# meduza01.net
KiCad netlist of a schematic drawn in EAGLE
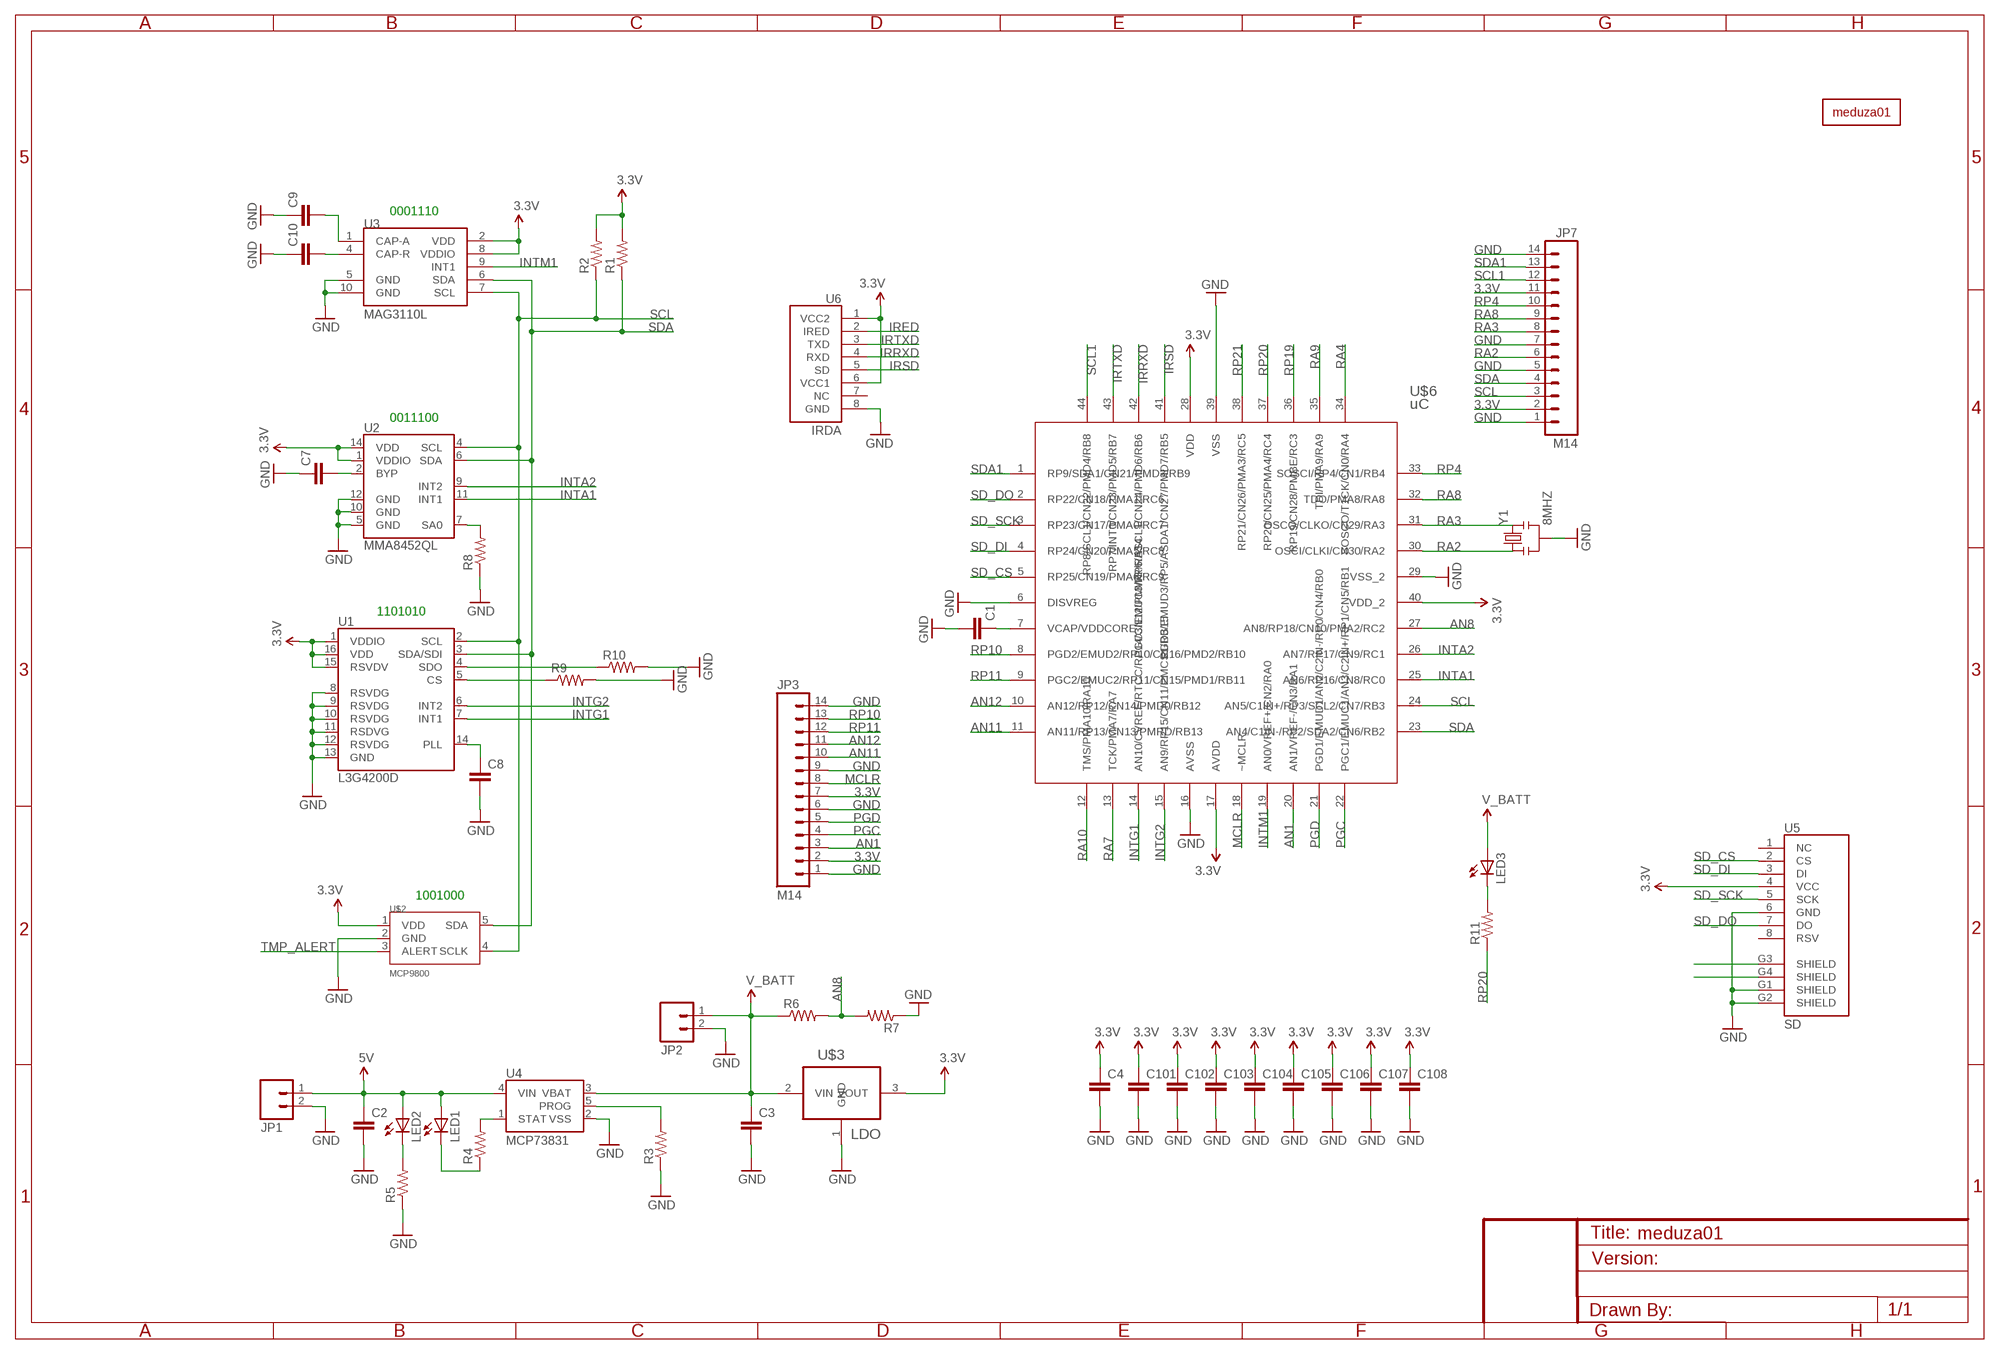
[diagram p0: schematic, sheet 1]

(export (version "E")
  (design (tool "Eeschema 10.0.6"))
  (components
    (comp (ref "C1")
      (value "CAP0603")
      (footprint "eagle-import:0603")
      (libsource (lib "eagle-import") (part "CAP0603"))
    )
    (comp (ref "C2")
      (value "CAP0805")
      (footprint "eagle-import:0805")
      (libsource (lib "eagle-import") (part "SparkFun-Passives_CAP0805"))
    )
    (comp (ref "C3")
      (value "CAP0805")
      (footprint "eagle-import:0805")
      (libsource (lib "eagle-import") (part "SparkFun-Passives_CAP0805"))
    )
    (comp (ref "C4")
      (value "CAP0603")
      (footprint "eagle-import:0603")
      (libsource (lib "eagle-import") (part "CAP0603"))
    )
    (comp (ref "C7")
      (value "CAP0603")
      (footprint "eagle-import:0603")
      (libsource (lib "eagle-import") (part "CAP0603"))
    )
    (comp (ref "C8")
      (value "CAP0603")
      (footprint "eagle-import:0603")
      (libsource (lib "eagle-import") (part "CAP0603"))
    )
    (comp (ref "C9")
      (value "CAP0603")
      (footprint "eagle-import:0603")
      (libsource (lib "eagle-import") (part "CAP0603"))
    )
    (comp (ref "C10")
      (value "CAP0603")
      (footprint "eagle-import:0603")
      (libsource (lib "eagle-import") (part "CAP0603"))
    )
    (comp (ref "C101")
      (value "CAP0603")
      (footprint "eagle-import:0603")
      (libsource (lib "eagle-import") (part "CAP0603"))
    )
    (comp (ref "C102")
      (value "CAP0603")
      (footprint "eagle-import:0603")
      (libsource (lib "eagle-import") (part "CAP0603"))
    )
    (comp (ref "C103")
      (value "CAP0603")
      (footprint "eagle-import:0603")
      (libsource (lib "eagle-import") (part "CAP0603"))
    )
    (comp (ref "C104")
      (value "CAP0603")
      (footprint "eagle-import:0603")
      (libsource (lib "eagle-import") (part "CAP0603"))
    )
    (comp (ref "C105")
      (value "CAP0603")
      (footprint "eagle-import:0603")
      (libsource (lib "eagle-import") (part "CAP0603"))
    )
    (comp (ref "C106")
      (value "CAP0603")
      (footprint "eagle-import:0603")
      (libsource (lib "eagle-import") (part "CAP0603"))
    )
    (comp (ref "C107")
      (value "CAP0603")
      (footprint "eagle-import:0603")
      (libsource (lib "eagle-import") (part "CAP0603"))
    )
    (comp (ref "C108")
      (value "CAP0603")
      (footprint "eagle-import:0603")
      (libsource (lib "eagle-import") (part "CAP0603"))
    )
    (comp (ref "JP1")
      (value "M02PTH")
      (footprint "eagle-import:1X02")
      (libsource (lib "eagle-import") (part "M02PTH"))
    )
    (comp (ref "JP2")
      (value "M02PTH")
      (footprint "eagle-import:1X02")
      (libsource (lib "eagle-import") (part "M02PTH"))
    )
    (comp (ref "JP3")
      (value "M14")
      (footprint "eagle-import:1X14")
      (libsource (lib "eagle-import") (part "M14"))
    )
    (comp (ref "JP7")
      (value "M14")
      (footprint "eagle-import:1X14")
      (libsource (lib "eagle-import") (part "M14"))
    )
    (comp (ref "LED1")
      (value "LED1206")
      (footprint "eagle-import:LED-1206")
      (libsource (lib "eagle-import") (part "LED1206"))
    )
    (comp (ref "LED2")
      (value "LED1206")
      (footprint "eagle-import:LED-1206")
      (libsource (lib "eagle-import") (part "LED1206"))
    )
    (comp (ref "LED3")
      (value "LED1206")
      (footprint "eagle-import:LED-1206")
      (libsource (lib "eagle-import") (part "LED1206"))
    )
    (comp (ref "R1")
      (value "RESISTOR0603")
      (footprint "eagle-import:0603")
      (libsource (lib "eagle-import") (part "RESISTOR0603"))
    )
    (comp (ref "R2")
      (value "RESISTOR0603")
      (footprint "eagle-import:0603")
      (libsource (lib "eagle-import") (part "RESISTOR0603"))
    )
    (comp (ref "R3")
      (value "RESISTOR0603")
      (footprint "eagle-import:0603")
      (libsource (lib "eagle-import") (part "RESISTOR0603"))
    )
    (comp (ref "R4")
      (value "RESISTOR0603")
      (footprint "eagle-import:0603")
      (libsource (lib "eagle-import") (part "RESISTOR0603"))
    )
    (comp (ref "R5")
      (value "RESISTOR0603")
      (footprint "eagle-import:0603")
      (libsource (lib "eagle-import") (part "RESISTOR0603"))
    )
    (comp (ref "R6")
      (value "RESISTOR0603")
      (footprint "eagle-import:0603")
      (libsource (lib "eagle-import") (part "RESISTOR0603"))
    )
    (comp (ref "R7")
      (value "RESISTOR0603")
      (footprint "eagle-import:0603")
      (libsource (lib "eagle-import") (part "RESISTOR0603"))
    )
    (comp (ref "R8")
      (value "RESISTOR0603")
      (footprint "eagle-import:0603")
      (libsource (lib "eagle-import") (part "RESISTOR0603"))
    )
    (comp (ref "R9")
      (value "RESISTOR0603")
      (footprint "eagle-import:0603")
      (libsource (lib "eagle-import") (part "RESISTOR0603"))
    )
    (comp (ref "R10")
      (value "RESISTOR0603")
      (footprint "eagle-import:0603")
      (libsource (lib "eagle-import") (part "RESISTOR0603"))
    )
    (comp (ref "R11")
      (value "RESISTOR0603")
      (footprint "eagle-import:0603")
      (libsource (lib "eagle-import") (part "RESISTOR0603"))
    )
    (comp (ref "U$1")
      (value "MEDUZA01")
      (footprint "eagle-import:MEDUZA01")
      (libsource (lib "eagle-import") (part "MEDUZA01"))
    )
    (comp (ref "U$2")
      (value "MCP9800")
      (footprint "eagle-import:SOT23-5")
      (libsource (lib "eagle-import") (part "MCP9800"))
    )
    (comp (ref "U$3")
      (value "LDO")
      (footprint "eagle-import:SOT89R")
      (libsource (lib "eagle-import") (part "MCP1700T-3302E/TTSOT89MCP1700-3N"))
    )
    (comp (ref "U$6")
      (value "uC")
      (footprint "eagle-import:QFP80P1200X1200X120-44N")
      (fields (field (name "MPN") "PIC24FJ64GA004-I/PT"))
      (libsource (lib "eagle-import") (part "PIC24FJ64GA004"))
    )
    (comp (ref "U1")
      (value "L3G4200D")
      (footprint "eagle-import:LGA16-4X4")
      (libsource (lib "eagle-import") (part "L3G4200D"))
    )
    (comp (ref "U2")
      (value "MMA8452QL")
      (footprint "eagle-import:QFN-16_0.5MM-EXTRA")
      (libsource (lib "eagle-import") (part "MMA8452QL"))
    )
    (comp (ref "U3")
      (value "MAG3110L")
      (footprint "eagle-import:DFN-10-EXTRA")
      (libsource (lib "eagle-import") (part "MAG3110L"))
    )
    (comp (ref "U4")
      (value "MCP73831")
      (footprint "eagle-import:SOT23-5")
      (libsource (lib "eagle-import") (part "MCP73831"))
    )
    (comp (ref "U5")
      (value "SD")
      (footprint "eagle-import:MOLEX-SD-47309")
      (libsource (lib "eagle-import") (part "USD-SOCKETMOLEX47309"))
    )
    (comp (ref "U6")
      (value "IRDA")
      (footprint "eagle-import:TFDU6300")
      (libsource (lib "eagle-import") (part "TFDU6300TFDU6300"))
    )
    (comp (ref "Y1")
      (value "8MHZ")
      (footprint "eagle-import:RESONATOR-SMD")
      (libsource (lib "eagle-import") (part "RESONATOR8MHZ"))
    )
  )
  (nets
    (net (code "1") (name "/AN1") (class "Default")
      (node (ref "JP3") (pin "3") (pinfunction "3_3") (pintype "passive"))
      (node (ref "U$6") (pin "20") (pinfunction "AN1/VREF-/CN3/RA1_20") (pintype "bidirectional"))
    )
    (net (code "2") (name "/AN8") (class "Default")
      (node (ref "R6") (pin "2") (pinfunction "2_2") (pintype "passive"))
      (node (ref "R7") (pin "2") (pinfunction "2_2") (pintype "passive"))
      (node (ref "U$6") (pin "27") (pinfunction "AN8/RP18/CN10/PMA2/RC2_27") (pintype "bidirectional"))
    )
    (net (code "3") (name "/AN11") (class "Default")
      (node (ref "JP3") (pin "10") (pinfunction "10_10") (pintype "passive"))
      (node (ref "U$6") (pin "11") (pinfunction "AN11/RP13/CN13/PMRD/RB13_11") (pintype "bidirectional"))
    )
    (net (code "4") (name "/AN12") (class "Default")
      (node (ref "JP3") (pin "11") (pinfunction "11_11") (pintype "passive"))
      (node (ref "U$6") (pin "10") (pinfunction "AN12/RP12/CN14/PMD0/RB12_10") (pintype "bidirectional"))
    )
    (net (code "5") (name "/INTA1") (class "Default")
      (node (ref "U$6") (pin "25") (pinfunction "AN6/RP16/CN8/RC0_25") (pintype "bidirectional"))
      (node (ref "U2") (pin "11") (pinfunction "INT1_11") (pintype "bidirectional"))
    )
    (net (code "6") (name "/INTA2") (class "Default")
      (node (ref "U$6") (pin "26") (pinfunction "AN7/RP17/CN9/RC1_26") (pintype "bidirectional"))
      (node (ref "U2") (pin "9") (pinfunction "INT2_9") (pintype "bidirectional"))
    )
    (net (code "7") (name "/INTG1") (class "Default")
      (node (ref "U$6") (pin "14") (pinfunction "AN10/CVREF/RTCC/RP14/CN12/PMWR/RB14_14") (pintype "bidirectional"))
      (node (ref "U1") (pin "7") (pinfunction "INT1_7") (pintype "bidirectional"))
    )
    (net (code "8") (name "/INTG2") (class "Default")
      (node (ref "U$6") (pin "15") (pinfunction "AN9/RP15/CN11/PMCS1/RB15_15") (pintype "bidirectional"))
      (node (ref "U1") (pin "6") (pinfunction "INT2_6") (pintype "bidirectional"))
    )
    (net (code "9") (name "/INTM1") (class "Default")
      (node (ref "U$6") (pin "19") (pinfunction "AN0/VREF+/CN2/RA0_19") (pintype "bidirectional"))
      (node (ref "U3") (pin "9") (pinfunction "INT1_9") (pintype "bidirectional"))
    )
    (net (code "10") (name "/IRED") (class "Default")
      (node (ref "U6") (pin "2") (pinfunction "IRED_2") (pintype "bidirectional"))
    )
    (net (code "11") (name "/IRRXD") (class "Default")
      (node (ref "U$6") (pin "42") (pinfunction "PGC3/EMUC3/RP6/ASCL1/CN24/PMD6/RB6_42") (pintype "bidirectional"))
      (node (ref "U6") (pin "4") (pinfunction "RXD_4") (pintype "bidirectional"))
    )
    (net (code "12") (name "/IRSD") (class "Default")
      (node (ref "U$6") (pin "41") (pinfunction "PGD3/EMUD3/RP5/ASDA1/CN27/PMD7/RB5_41") (pintype "bidirectional"))
      (node (ref "U6") (pin "5") (pinfunction "SD_5") (pintype "bidirectional"))
    )
    (net (code "13") (name "/IRTXD") (class "Default")
      (node (ref "U$6") (pin "43") (pinfunction "RP7/INT0/CN23/PMD5/RB7_43") (pintype "bidirectional"))
      (node (ref "U6") (pin "3") (pinfunction "TXD_3") (pintype "bidirectional"))
    )
    (net (code "14") (name "/MCLR") (class "Default")
      (node (ref "JP3") (pin "8") (pinfunction "8_8") (pintype "passive"))
      (node (ref "U$6") (pin "18") (pinfunction "~{MCLR}_18") (pintype "bidirectional"))
    )
    (net (code "15") (name "/PGC") (class "Default")
      (node (ref "JP3") (pin "4") (pinfunction "4_4") (pintype "passive"))
      (node (ref "U$6") (pin "22") (pinfunction "PGC1/EMUC1/AN3/C2IN+/RP1/CN5/RB1_22") (pintype "bidirectional"))
    )
    (net (code "16") (name "/PGD") (class "Default")
      (node (ref "JP3") (pin "5") (pinfunction "5_5") (pintype "passive"))
      (node (ref "U$6") (pin "21") (pinfunction "PGD1/EMUD1/AN2/C2IN-/RP0/CN4/RB0_21") (pintype "bidirectional"))
    )
    (net (code "17") (name "/RA2") (class "Default")
      (node (ref "JP7") (pin "6") (pinfunction "6_6") (pintype "passive"))
      (node (ref "U$6") (pin "30") (pinfunction "OSCI/CLKI/CN30/RA2_30") (pintype "bidirectional"))
      (node (ref "Y1") (pin "1") (pinfunction "1_1") (pintype "passive"))
    )
    (net (code "18") (name "/RA3") (class "Default")
      (node (ref "JP7") (pin "8") (pinfunction "8_8") (pintype "passive"))
      (node (ref "U$6") (pin "31") (pinfunction "OSCO/CLKO/CN29/RA3_31") (pintype "bidirectional"))
      (node (ref "Y1") (pin "3") (pinfunction "3_3") (pintype "passive"))
    )
    (net (code "19") (name "/RA4") (class "Default")
      (node (ref "U$6") (pin "34") (pinfunction "SOSCO/T1CK/CN0/RA4_34") (pintype "bidirectional"))
    )
    (net (code "20") (name "/RA7") (class "Default")
      (node (ref "U$6") (pin "13") (pinfunction "TCK/PMA7/RA7_13") (pintype "bidirectional"))
    )
    (net (code "21") (name "/RA8") (class "Default")
      (node (ref "JP7") (pin "9") (pinfunction "9_9") (pintype "passive"))
      (node (ref "U$6") (pin "32") (pinfunction "TDO/PMA8/RA8_32") (pintype "bidirectional"))
    )
    (net (code "22") (name "/RA9") (class "Default")
      (node (ref "U$6") (pin "35") (pinfunction "TDI/PMA9/RA9_35") (pintype "bidirectional"))
    )
    (net (code "23") (name "/RA10") (class "Default")
      (node (ref "U$6") (pin "12") (pinfunction "TMS/PMA10/RA10_12") (pintype "bidirectional"))
    )
    (net (code "24") (name "/RP4") (class "Default")
      (node (ref "JP7") (pin "10") (pinfunction "10_10") (pintype "passive"))
      (node (ref "U$6") (pin "33") (pinfunction "SOSCI/RP4/CN1/RB4_33") (pintype "bidirectional"))
    )
    (net (code "25") (name "/RP10") (class "Default")
      (node (ref "JP3") (pin "13") (pinfunction "13_13") (pintype "passive"))
      (node (ref "U$6") (pin "8") (pinfunction "PGD2/EMUD2/RP10/CN16/PMD2/RB10_8") (pintype "bidirectional"))
    )
    (net (code "26") (name "/RP11") (class "Default")
      (node (ref "JP3") (pin "12") (pinfunction "12_12") (pintype "passive"))
      (node (ref "U$6") (pin "9") (pinfunction "PGC2/EMUC2/RP11/CN15/PMD1/RB11_9") (pintype "bidirectional"))
    )
    (net (code "27") (name "/RP19") (class "Default")
      (node (ref "U$6") (pin "36") (pinfunction "RP19/CN28/PMBE/RC3_36") (pintype "bidirectional"))
    )
    (net (code "28") (name "/RP20") (class "Default")
      (node (ref "R11") (pin "1") (pinfunction "1_1") (pintype "passive"))
      (node (ref "U$6") (pin "37") (pinfunction "RP20/CN25/PMA4/RC4_37") (pintype "bidirectional"))
    )
    (net (code "29") (name "/RP21") (class "Default")
      (node (ref "U$6") (pin "38") (pinfunction "RP21/CN26/PMA3/RC5_38") (pintype "bidirectional"))
    )
    (net (code "30") (name "/SCL") (class "Default")
      (node (ref "JP7") (pin "3") (pinfunction "3_3") (pintype "passive"))
      (node (ref "R2") (pin "1") (pinfunction "1_1") (pintype "passive"))
      (node (ref "U$2") (pin "4") (pinfunction "SCLK_4") (pintype "input"))
      (node (ref "U$6") (pin "24") (pinfunction "AN5/C1IN+/RP3/SCL2/CN7/RB3_24") (pintype "bidirectional"))
      (node (ref "U1") (pin "2") (pinfunction "SCL_2") (pintype "bidirectional"))
      (node (ref "U2") (pin "4") (pinfunction "SCL_4") (pintype "bidirectional"))
      (node (ref "U3") (pin "7") (pinfunction "SCL_7") (pintype "bidirectional"))
    )
    (net (code "31") (name "/SCL1") (class "Default")
      (node (ref "JP7") (pin "12") (pinfunction "12_12") (pintype "passive"))
      (node (ref "U$6") (pin "44") (pinfunction "RP8/SCL1/CN22/PMD4/RB8_44") (pintype "bidirectional"))
    )
    (net (code "32") (name "/SDA") (class "Default")
      (node (ref "JP7") (pin "4") (pinfunction "4_4") (pintype "passive"))
      (node (ref "R1") (pin "1") (pinfunction "1_1") (pintype "passive"))
      (node (ref "U$2") (pin "5") (pinfunction "SDA_5") (pintype "bidirectional"))
      (node (ref "U$6") (pin "23") (pinfunction "AN4/C1IN-/RP2/SDA2/CN6/RB2_23") (pintype "bidirectional"))
      (node (ref "U1") (pin "3") (pinfunction "SDA/SDI_3") (pintype "bidirectional"))
      (node (ref "U2") (pin "6") (pinfunction "SDA_6") (pintype "bidirectional"))
      (node (ref "U3") (pin "6") (pinfunction "SDA_6") (pintype "bidirectional"))
    )
    (net (code "33") (name "/SDA1") (class "Default")
      (node (ref "JP7") (pin "13") (pinfunction "13_13") (pintype "passive"))
      (node (ref "U$6") (pin "1") (pinfunction "RP9/SDA1/CN21/PMD3/RB9_1") (pintype "bidirectional"))
    )
    (net (code "34") (name "/SD_CS") (class "Default")
      (node (ref "U$6") (pin "5") (pinfunction "RP25/CN19/PMA6/RC9_5") (pintype "bidirectional"))
      (node (ref "U5") (pin "2") (pinfunction "CS_2") (pintype "bidirectional"))
    )
    (net (code "35") (name "/SD_DI") (class "Default")
      (node (ref "U$6") (pin "4") (pinfunction "RP24/CN20/PMA5/RC8_4") (pintype "bidirectional"))
      (node (ref "U5") (pin "3") (pinfunction "DI_3") (pintype "bidirectional"))
    )
    (net (code "36") (name "/SD_DO") (class "Default")
      (node (ref "U$6") (pin "2") (pinfunction "RP22/CN18/PMA1/RC6_2") (pintype "bidirectional"))
      (node (ref "U5") (pin "7") (pinfunction "DO_7") (pintype "bidirectional"))
    )
    (net (code "37") (name "/SD_SCK") (class "Default")
      (node (ref "U$6") (pin "3") (pinfunction "RP23/CN17/PMA0/RC7_3") (pintype "bidirectional"))
      (node (ref "U5") (pin "5") (pinfunction "SCK_5") (pintype "bidirectional"))
    )
    (net (code "38") (name "/TMP_ALERT") (class "Default")
      (node (ref "U$2") (pin "3") (pinfunction "ALERT_3") (pintype "output"))
    )
    (net (code "39") (name "3.3V") (class "Default")
      (node (ref "C101") (pin "1") (pinfunction "1_1") (pintype "passive"))
      (node (ref "C102") (pin "1") (pinfunction "1_1") (pintype "passive"))
      (node (ref "C103") (pin "1") (pinfunction "1_1") (pintype "passive"))
      (node (ref "C104") (pin "1") (pinfunction "1_1") (pintype "passive"))
      (node (ref "C105") (pin "1") (pinfunction "1_1") (pintype "passive"))
      (node (ref "C106") (pin "1") (pinfunction "1_1") (pintype "passive"))
      (node (ref "C107") (pin "1") (pinfunction "1_1") (pintype "passive"))
      (node (ref "C108") (pin "1") (pinfunction "1_1") (pintype "passive"))
      (node (ref "C4") (pin "1") (pinfunction "1_1") (pintype "passive"))
      (node (ref "JP3") (pin "2") (pinfunction "2_2") (pintype "passive"))
      (node (ref "JP3") (pin "7") (pinfunction "7_7") (pintype "passive"))
      (node (ref "JP7") (pin "11") (pinfunction "11_11") (pintype "passive"))
      (node (ref "JP7") (pin "2") (pinfunction "2_2") (pintype "passive"))
      (node (ref "R1") (pin "2") (pinfunction "2_2") (pintype "passive"))
      (node (ref "R2") (pin "2") (pinfunction "2_2") (pintype "passive"))
      (node (ref "U$2") (pin "1") (pinfunction "VDD_1") (pintype "power_in"))
      (node (ref "U$3") (pin "3") (pinfunction "VOUT_3") (pintype "output"))
      (node (ref "U$6") (pin "17") (pinfunction "AVDD_17") (pintype "power_in"))
      (node (ref "U$6") (pin "28") (pinfunction "VDD_28") (pintype "power_in"))
      (node (ref "U$6") (pin "40") (pinfunction "VDD_2_40") (pintype "power_in"))
      (node (ref "U1") (pin "1") (pinfunction "VDDIO_1") (pintype "bidirectional"))
      (node (ref "U1") (pin "15") (pinfunction "RSVDV_15") (pintype "bidirectional"))
      (node (ref "U1") (pin "16") (pinfunction "VDD_16") (pintype "bidirectional"))
      (node (ref "U2") (pin "1") (pinfunction "VDDIO_1") (pintype "bidirectional"))
      (node (ref "U2") (pin "14") (pinfunction "VDD_14") (pintype "bidirectional"))
      (node (ref "U3") (pin "2") (pinfunction "VDD_2") (pintype "bidirectional"))
      (node (ref "U3") (pin "8") (pinfunction "VDDIO_8") (pintype "bidirectional"))
      (node (ref "U5") (pin "4") (pinfunction "VCC_4") (pintype "bidirectional"))
      (node (ref "U6") (pin "1") (pinfunction "VCC2_1") (pintype "bidirectional"))
      (node (ref "U6") (pin "6") (pinfunction "VCC1_6") (pintype "bidirectional"))
    )
    (net (code "40") (name "5V") (class "Default")
      (node (ref "C2") (pin "1") (pinfunction "1_1") (pintype "passive"))
      (node (ref "JP1") (pin "1") (pinfunction "1_1") (pintype "passive"))
      (node (ref "LED1") (pin "A") (pinfunction "A_A") (pintype "passive"))
      (node (ref "LED2") (pin "A") (pinfunction "A_A") (pintype "passive"))
      (node (ref "U4") (pin "4") (pinfunction "VIN_4") (pintype "power_in"))
    )
    (net (code "41") (name "GND") (class "Default")
      (node (ref "C1") (pin "2") (pinfunction "2_2") (pintype "passive"))
      (node (ref "C10") (pin "1") (pinfunction "1_1") (pintype "passive"))
      (node (ref "C101") (pin "2") (pinfunction "2_2") (pintype "passive"))
      (node (ref "C102") (pin "2") (pinfunction "2_2") (pintype "passive"))
      (node (ref "C103") (pin "2") (pinfunction "2_2") (pintype "passive"))
      (node (ref "C104") (pin "2") (pinfunction "2_2") (pintype "passive"))
      (node (ref "C105") (pin "2") (pinfunction "2_2") (pintype "passive"))
      (node (ref "C106") (pin "2") (pinfunction "2_2") (pintype "passive"))
      (node (ref "C107") (pin "2") (pinfunction "2_2") (pintype "passive"))
      (node (ref "C108") (pin "2") (pinfunction "2_2") (pintype "passive"))
      (node (ref "C2") (pin "2") (pinfunction "2_2") (pintype "passive"))
      (node (ref "C3") (pin "2") (pinfunction "2_2") (pintype "passive"))
      (node (ref "C4") (pin "2") (pinfunction "2_2") (pintype "passive"))
      (node (ref "C7") (pin "1") (pinfunction "1_1") (pintype "passive"))
      (node (ref "C8") (pin "2") (pinfunction "2_2") (pintype "passive"))
      (node (ref "C9") (pin "1") (pinfunction "1_1") (pintype "passive"))
      (node (ref "JP1") (pin "2") (pinfunction "2_2") (pintype "passive"))
      (node (ref "JP2") (pin "2") (pinfunction "2_2") (pintype "passive"))
      (node (ref "JP3") (pin "1") (pinfunction "1_1") (pintype "passive"))
      (node (ref "JP3") (pin "14") (pinfunction "14_14") (pintype "passive"))
      (node (ref "JP3") (pin "6") (pinfunction "6_6") (pintype "passive"))
      (node (ref "JP3") (pin "9") (pinfunction "9_9") (pintype "passive"))
      (node (ref "JP7") (pin "1") (pinfunction "1_1") (pintype "passive"))
      (node (ref "JP7") (pin "14") (pinfunction "14_14") (pintype "passive"))
      (node (ref "JP7") (pin "5") (pinfunction "5_5") (pintype "passive"))
      (node (ref "JP7") (pin "7") (pinfunction "7_7") (pintype "passive"))
      (node (ref "R10") (pin "2") (pinfunction "2_2") (pintype "passive"))
      (node (ref "R3") (pin "1") (pinfunction "1_1") (pintype "passive"))
      (node (ref "R5") (pin "1") (pinfunction "1_1") (pintype "passive"))
      (node (ref "R7") (pin "1") (pinfunction "1_1") (pintype "passive"))
      (node (ref "R8") (pin "1") (pinfunction "1_1") (pintype "passive"))
      (node (ref "R9") (pin "2") (pinfunction "2_2") (pintype "passive"))
      (node (ref "U$2") (pin "2") (pinfunction "GND_2") (pintype "passive"))
      (node (ref "U$3") (pin "1") (pinfunction "GND_1") (pintype "passive"))
      (node (ref "U$6") (pin "16") (pinfunction "AVSS_16") (pintype "power_in"))
      (node (ref "U$6") (pin "29") (pinfunction "VSS_2_29") (pintype "power_in"))
      (node (ref "U$6") (pin "39") (pinfunction "VSS_39") (pintype "power_in"))
      (node (ref "U$6") (pin "6") (pinfunction "DISVREG_6") (pintype "passive"))
      (node (ref "U1") (pin "10") (pinfunction "RSVDG_10") (pintype "bidirectional"))
      (node (ref "U1") (pin "11") (pinfunction "RSDVG_11") (pintype "bidirectional"))
      (node (ref "U1") (pin "12") (pinfunction "RSVDG_12") (pintype "bidirectional"))
      (node (ref "U1") (pin "13") (pinfunction "GND_13") (pintype "bidirectional"))
      (node (ref "U1") (pin "8") (pinfunction "RSVDG_8") (pintype "bidirectional"))
      (node (ref "U1") (pin "9") (pinfunction "RSVDG_9") (pintype "bidirectional"))
      (node (ref "U2") (pin "10") (pinfunction "GND_10") (pintype "bidirectional"))
      (node (ref "U2") (pin "12") (pinfunction "GND_12") (pintype "bidirectional"))
      (node (ref "U2") (pin "5") (pinfunction "GND_5") (pintype "bidirectional"))
      (node (ref "U3") (pin "10") (pinfunction "GND_10") (pintype "bidirectional"))
      (node (ref "U3") (pin "5") (pinfunction "GND_5") (pintype "bidirectional"))
      (node (ref "U4") (pin "2") (pinfunction "VSS_2") (pintype "power_in"))
      (node (ref "U5") (pin "6") (pinfunction "GND_6") (pintype "bidirectional"))
      (node (ref "U5") (pin "G1") (pinfunction "SHIELD_G1") (pintype "bidirectional"))
      (node (ref "U5") (pin "G2") (pinfunction "SHIELD_G2") (pintype "bidirectional"))
      (node (ref "U6") (pin "8") (pinfunction "GND_8") (pintype "bidirectional"))
      (node (ref "Y1") (pin "2") (pinfunction "2_2") (pintype "passive"))
    )
    (net (code "42") (name "Net-(LED1-PadC)") (class "Default")
      (node (ref "LED1") (pin "C") (pinfunction "C_C") (pintype "passive"))
      (node (ref "R4") (pin "1") (pinfunction "1_1") (pintype "passive"))
    )
    (net (code "43") (name "Net-(LED2-PadC)") (class "Default")
      (node (ref "LED2") (pin "C") (pinfunction "C_C") (pintype "passive"))
      (node (ref "R5") (pin "2") (pinfunction "2_2") (pintype "passive"))
    )
    (net (code "44") (name "Net-(LED3-PadC)") (class "Default")
      (node (ref "LED3") (pin "C") (pinfunction "C_C") (pintype "passive"))
      (node (ref "R11") (pin "2") (pinfunction "2_2") (pintype "passive"))
    )
    (net (code "45") (name "Net-(U$6-VCAP{slash}VDDCORE)") (class "Default")
      (node (ref "C1") (pin "1") (pinfunction "1_1") (pintype "passive"))
      (node (ref "U$6") (pin "7") (pinfunction "VCAP/VDDCORE_7") (pintype "power_in"))
    )
    (net (code "46") (name "Net-(U1-CS)") (class "Default")
      (node (ref "R9") (pin "1") (pinfunction "1_1") (pintype "passive"))
      (node (ref "U1") (pin "5") (pinfunction "CS_5") (pintype "bidirectional"))
    )
    (net (code "47") (name "Net-(U1-PLL)") (class "Default")
      (node (ref "C8") (pin "1") (pinfunction "1_1") (pintype "passive"))
      (node (ref "U1") (pin "14") (pinfunction "PLL_14") (pintype "bidirectional"))
    )
    (net (code "48") (name "Net-(U1-SDO)") (class "Default")
      (node (ref "R10") (pin "1") (pinfunction "1_1") (pintype "passive"))
      (node (ref "U1") (pin "4") (pinfunction "SDO_4") (pintype "bidirectional"))
    )
    (net (code "49") (name "Net-(U2-BYP)") (class "Default")
      (node (ref "C7") (pin "2") (pinfunction "2_2") (pintype "passive"))
      (node (ref "U2") (pin "2") (pinfunction "BYP_2") (pintype "bidirectional"))
    )
    (net (code "50") (name "Net-(U2-SA0)") (class "Default")
      (node (ref "R8") (pin "2") (pinfunction "2_2") (pintype "passive"))
      (node (ref "U2") (pin "7") (pinfunction "SA0_7") (pintype "bidirectional"))
    )
    (net (code "51") (name "Net-(U3-CAP-A)") (class "Default")
      (node (ref "C9") (pin "2") (pinfunction "2_2") (pintype "passive"))
      (node (ref "U3") (pin "1") (pinfunction "CAP-A_1") (pintype "bidirectional"))
    )
    (net (code "52") (name "Net-(U3-CAP-R)") (class "Default")
      (node (ref "C10") (pin "2") (pinfunction "2_2") (pintype "passive"))
      (node (ref "U3") (pin "4") (pinfunction "CAP-R_4") (pintype "bidirectional"))
    )
    (net (code "53") (name "Net-(U4-PROG)") (class "Default")
      (node (ref "R3") (pin "2") (pinfunction "2_2") (pintype "passive"))
      (node (ref "U4") (pin "5") (pinfunction "PROG_5") (pintype "input"))
    )
    (net (code "54") (name "Net-(U4-STAT)") (class "Default")
      (node (ref "R4") (pin "2") (pinfunction "2_2") (pintype "passive"))
      (node (ref "U4") (pin "1") (pinfunction "STAT_1") (pintype "output"))
    )
    (net (code "55") (name "V_BATT") (class "Default")
      (node (ref "C3") (pin "1") (pinfunction "1_1") (pintype "passive"))
      (node (ref "JP2") (pin "1") (pinfunction "1_1") (pintype "passive"))
      (node (ref "LED3") (pin "A") (pinfunction "A_A") (pintype "passive"))
      (node (ref "R6") (pin "1") (pinfunction "1_1") (pintype "passive"))
      (node (ref "U$3") (pin "2") (pinfunction "VIN_2") (pintype "input"))
      (node (ref "U4") (pin "3") (pinfunction "VBAT_3") (pintype "power_in"))
    )
    (net (code "56") (name "unconnected-(U5-NC-Pad1)") (class "Default")
      (node (ref "U5") (pin "1") (pinfunction "NC_1") (pintype "bidirectional"))
    )
    (net (code "57") (name "unconnected-(U5-RSV-Pad8)") (class "Default")
      (node (ref "U5") (pin "8") (pinfunction "RSV_8") (pintype "bidirectional"))
    )
    (net (code "58") (name "unconnected-(U5-SHIELD-PadG3)") (class "Default")
      (node (ref "U5") (pin "G3") (pinfunction "SHIELD_G3") (pintype "bidirectional"))
    )
    (net (code "59") (name "unconnected-(U5-SHIELD-PadG4)") (class "Default")
      (node (ref "U5") (pin "G4") (pinfunction "SHIELD_G4") (pintype "bidirectional"))
    )
    (net (code "60") (name "unconnected-(U6-NC-Pad7)") (class "Default")
      (node (ref "U6") (pin "7") (pinfunction "NC_7") (pintype "bidirectional"))
    )
  )
)
